# 16_HDMI.net
KiCad netlist of a schematic drawn in Altium Designer
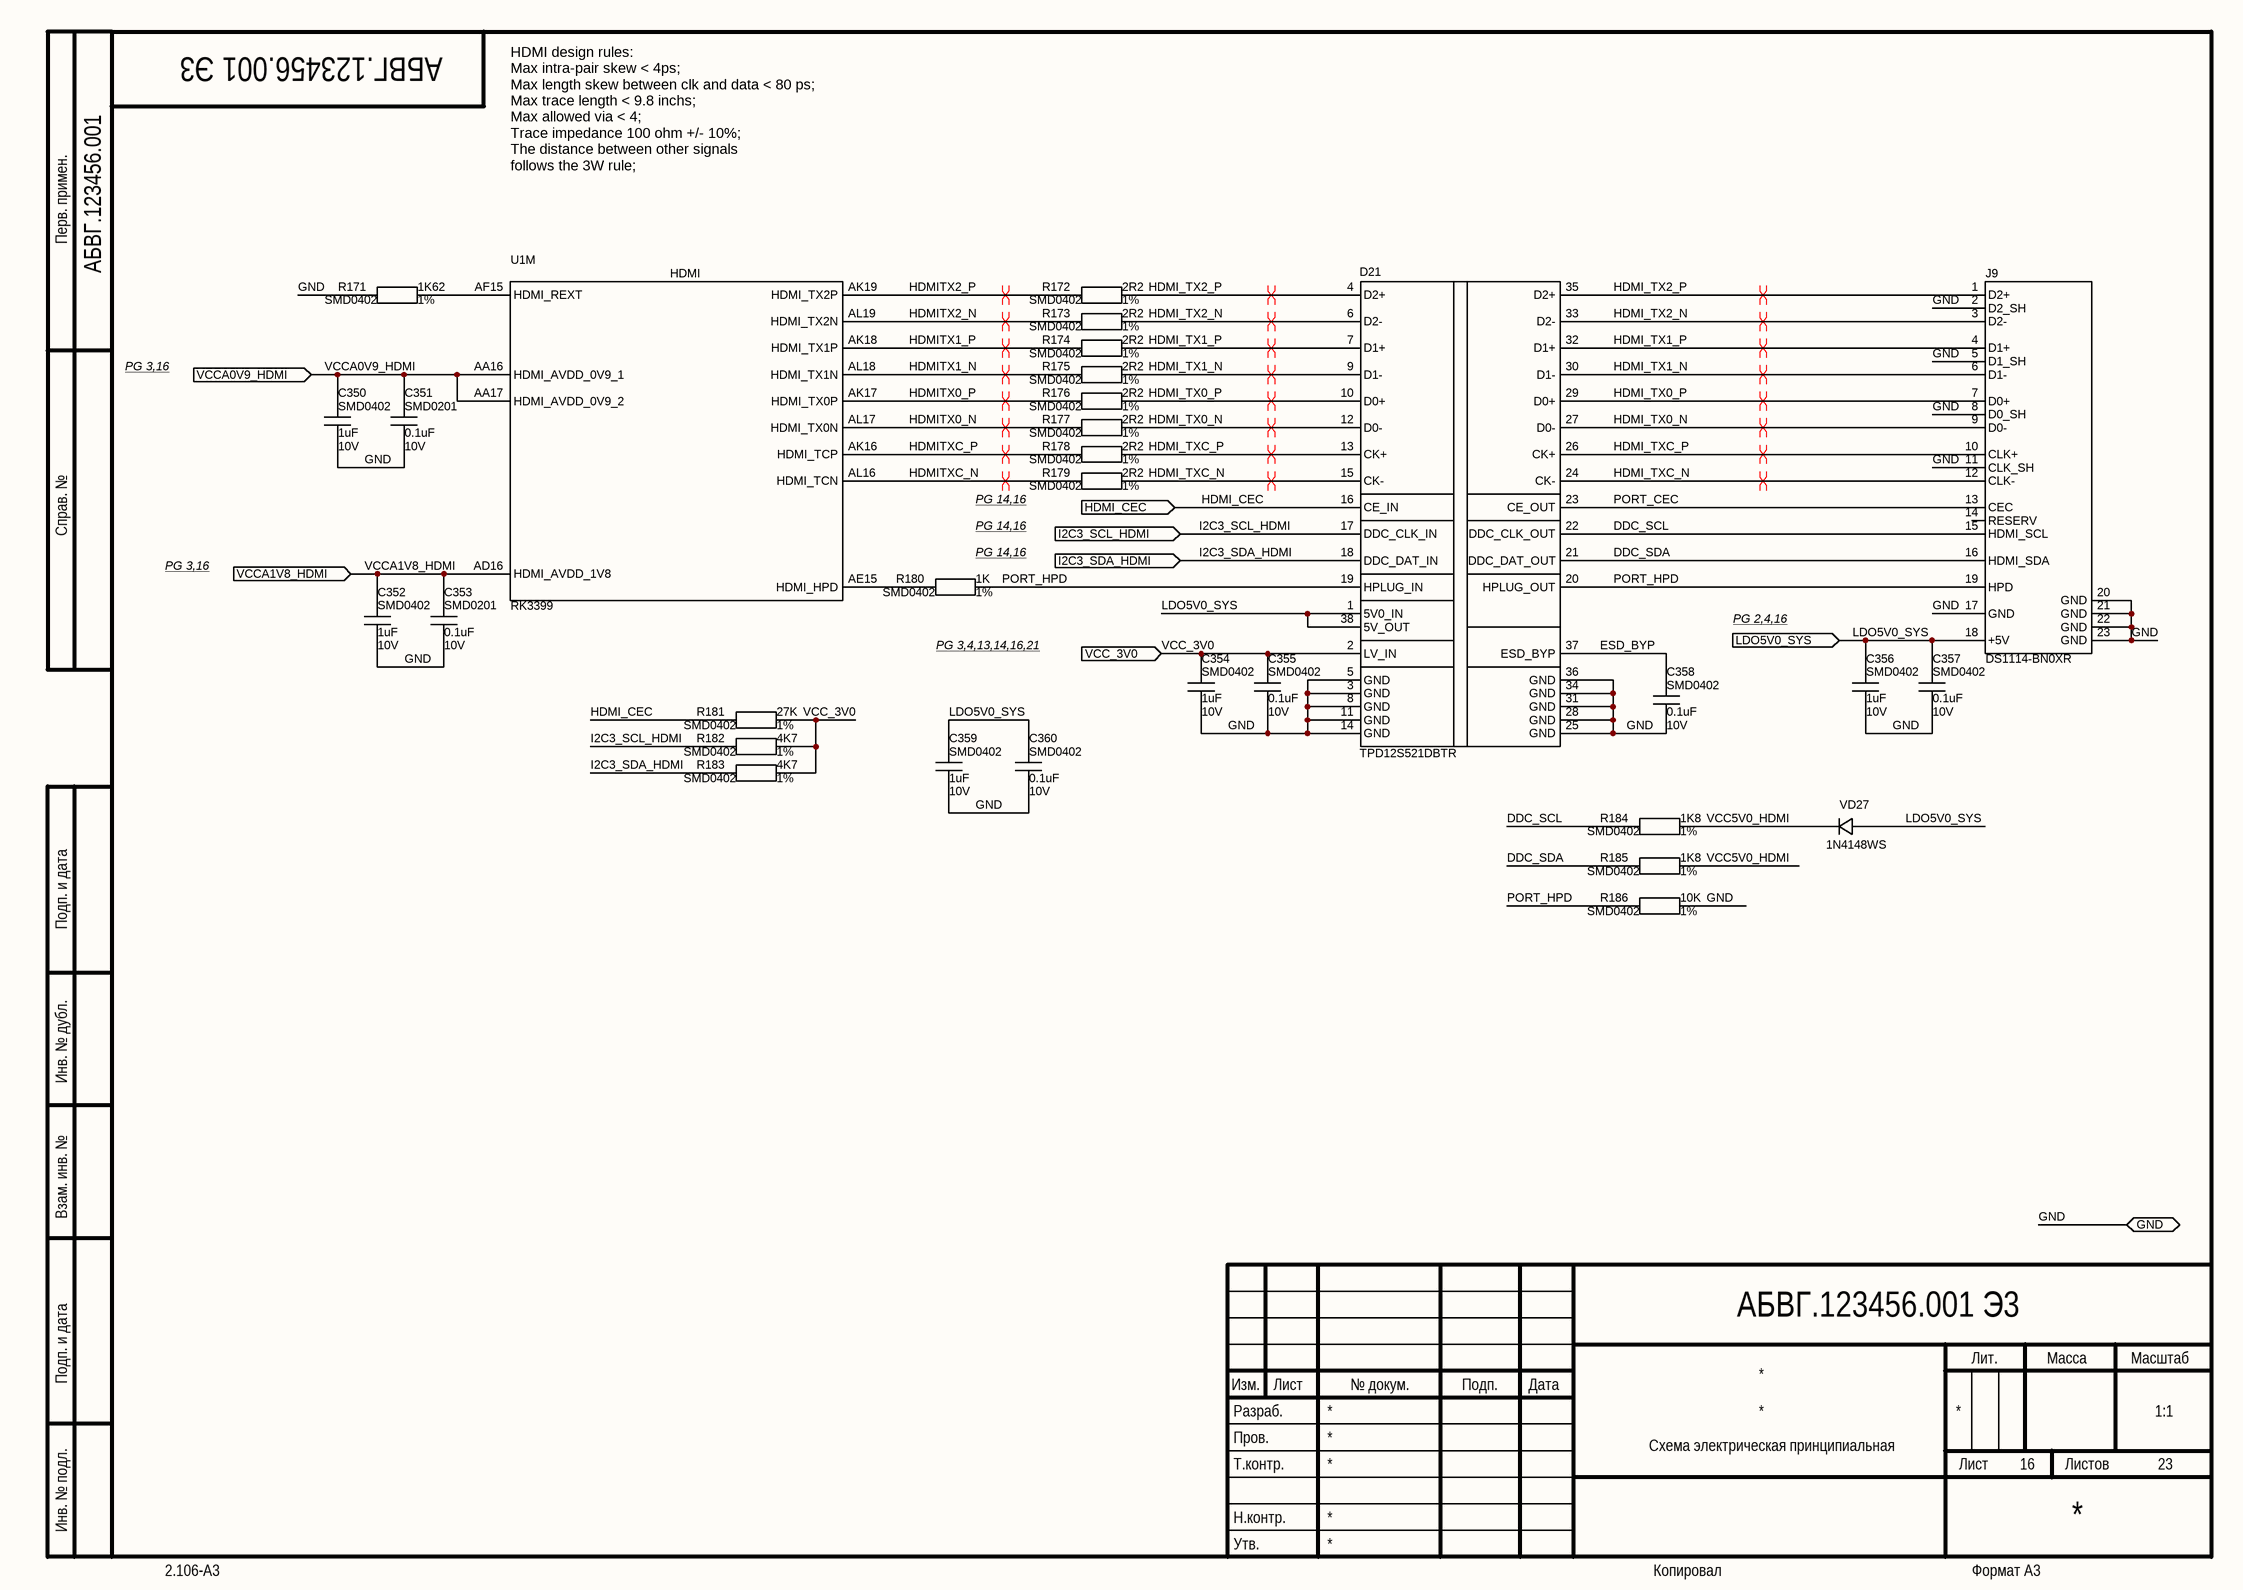
[diagram p0: 16 HDMI.SchDoc]

(export (version "E")
  (design (tool "Eeschema 10.0.6"))
  (components
    (comp (ref "C350")
      (value "1uF")
      (footprint "Didur_PcbLib_1:CAP_SMD_0402")
      (fields
        (field (name "PACKAGE") "SMD0402")
        (field (name "PARTNUMBER") "CC0402KRX5R6BB105")
        (field (name "VOLTAGE") "10V")
      )
      (libsource (lib "Didur_SchLib_1") (part "Ceramic_Cap"))
    )
    (comp (ref "C351")
      (value "0.1uF")
      (footprint "Didur_PcbLib_1:CAP_SMD_0201")
      (fields
        (field (name "PACKAGE") "SMD0201")
        (field (name "PARTNUMBER") "CC0201KRX5R6BB104")
        (field (name "VOLTAGE") "10V")
      )
      (libsource (lib "Didur_SchLib_1") (part "Ceramic_Cap"))
    )
    (comp (ref "C352")
      (value "1uF")
      (footprint "Didur_PcbLib_1:CAP_SMD_0402_small")
      (fields
        (field (name "PACKAGE") "SMD0402")
        (field (name "PARTNUMBER") "CC0402KRX5R6BB105")
        (field (name "VOLTAGE") "10V")
      )
      (libsource (lib "Didur_SchLib_1") (part "Ceramic_Cap"))
    )
    (comp (ref "C353")
      (value "0.1uF")
      (footprint "Didur_PcbLib_1:CAP_SMD_0201")
      (fields
        (field (name "PACKAGE") "SMD0201")
        (field (name "PARTNUMBER") "CC0201KRX5R6BB104")
        (field (name "VOLTAGE") "10V")
      )
      (libsource (lib "Didur_SchLib_1") (part "Ceramic_Cap"))
    )
    (comp (ref "C354")
      (value "1uF")
      (footprint "Didur_PcbLib_1:CAP_SMD_0402")
      (fields
        (field (name "PACKAGE") "SMD0402")
        (field (name "PARTNUMBER") "CC0402KRX5R6BB105")
        (field (name "VOLTAGE") "10V")
      )
      (libsource (lib "Didur_SchLib_1") (part "Ceramic_Cap"))
    )
    (comp (ref "C355")
      (value "0.1uF")
      (footprint "Didur_PcbLib_1:CAP_SMD_0402")
      (fields
        (field (name "PACKAGE") "SMD0402")
        (field (name "PARTNUMBER") "CC0402KRX5R6BB104")
        (field (name "VOLTAGE") "10V")
      )
      (libsource (lib "Didur_SchLib_1") (part "Ceramic_Cap"))
    )
    (comp (ref "C356")
      (value "1uF")
      (footprint "Didur_PcbLib_1:CAP_SMD_0402")
      (fields
        (field (name "PACKAGE") "SMD0402")
        (field (name "PARTNUMBER") "CC0402KRX5R6BB105")
        (field (name "VOLTAGE") "10V")
      )
      (libsource (lib "Didur_SchLib_1") (part "Ceramic_Cap"))
    )
    (comp (ref "C357")
      (value "0.1uF")
      (footprint "Didur_PcbLib_1:CAP_SMD_0402")
      (fields
        (field (name "PACKAGE") "SMD0402")
        (field (name "PARTNUMBER") "CC0402KRX5R6BB104")
        (field (name "VOLTAGE") "10V")
      )
      (libsource (lib "Didur_SchLib_1") (part "Ceramic_Cap"))
    )
    (comp (ref "C358")
      (value "0.1uF")
      (footprint "Didur_PcbLib_1:CAP_SMD_0402")
      (fields
        (field (name "PACKAGE") "SMD0402")
        (field (name "PARTNUMBER") "CC0402KRX5R6BB104")
        (field (name "VOLTAGE") "10V")
      )
      (libsource (lib "Didur_SchLib_1") (part "Ceramic_Cap"))
    )
    (comp (ref "C359")
      (value "1uF")
      (footprint "Didur_PcbLib_1:CAP_SMD_0402")
      (fields
        (field (name "PACKAGE") "SMD0402")
        (field (name "PARTNUMBER") "CC0402KRX5R6BB105")
        (field (name "VOLTAGE") "10V")
      )
      (libsource (lib "Didur_SchLib_1") (part "Ceramic_Cap"))
    )
    (comp (ref "C360")
      (value "0.1uF")
      (footprint "Didur_PcbLib_1:CAP_SMD_0402")
      (fields
        (field (name "PACKAGE") "SMD0402")
        (field (name "PARTNUMBER") "CC0402KRX5R6BB104")
        (field (name "VOLTAGE") "10V")
      )
      (libsource (lib "Didur_SchLib_1") (part "Ceramic_Cap"))
    )
    (comp (ref "D21")
      (value "TPD12S521DBTR")
      (footprint "Didur_PcbLib_1:TSSOP-38")
      (libsource (lib "Didur_SchLib_1") (part "TPD12S521DBTR"))
    )
    (comp (ref "J9")
      (value "DS1114-BN0XR")
      (footprint "Didur_PcbLib_1:DS1114-BN0XR")
      (libsource (lib "Didur_SchLib_1") (part "HDMI_A_1"))
    )
    (comp (ref "R171")
      (value "1K62")
      (footprint "Didur_PcbLib_1:RES_SMD_0402_SMALL")
      (fields
        (field (name "PACKAGE") "SMD0402")
        (field (name "PARTNUMBER") "RC0402FR-071K62L")
        (field (name "TOLERANCE") "1%")
      )
      (libsource (lib "Didur_SchLib_1") (part "Chip_Res"))
    )
    (comp (ref "R172")
      (value "2R2")
      (footprint "Didur_PcbLib_1:RES_SMD_0402")
      (fields
        (field (name "PACKAGE") "SMD0402")
        (field (name "PARTNUMBER") "RC0402FR-072R2L")
        (field (name "TOLERANCE") "1%")
      )
      (libsource (lib "Didur_SchLib_1") (part "Chip_Res"))
    )
    (comp (ref "R173")
      (value "2R2")
      (footprint "Didur_PcbLib_1:RES_SMD_0402")
      (fields
        (field (name "PACKAGE") "SMD0402")
        (field (name "PARTNUMBER") "RC0402FR-072R2L")
        (field (name "TOLERANCE") "1%")
      )
      (libsource (lib "Didur_SchLib_1") (part "Chip_Res"))
    )
    (comp (ref "R174")
      (value "2R2")
      (footprint "Didur_PcbLib_1:RES_SMD_0402")
      (fields
        (field (name "PACKAGE") "SMD0402")
        (field (name "PARTNUMBER") "RC0402FR-072R2L")
        (field (name "TOLERANCE") "1%")
      )
      (libsource (lib "Didur_SchLib_1") (part "Chip_Res"))
    )
    (comp (ref "R175")
      (value "2R2")
      (footprint "Didur_PcbLib_1:RES_SMD_0402")
      (fields
        (field (name "PACKAGE") "SMD0402")
        (field (name "PARTNUMBER") "RC0402FR-072R2L")
        (field (name "TOLERANCE") "1%")
      )
      (libsource (lib "Didur_SchLib_1") (part "Chip_Res"))
    )
    (comp (ref "R176")
      (value "2R2")
      (footprint "Didur_PcbLib_1:RES_SMD_0402")
      (fields
        (field (name "PACKAGE") "SMD0402")
        (field (name "PARTNUMBER") "RC0402FR-072R2L")
        (field (name "TOLERANCE") "1%")
      )
      (libsource (lib "Didur_SchLib_1") (part "Chip_Res"))
    )
    (comp (ref "R177")
      (value "2R2")
      (footprint "Didur_PcbLib_1:RES_SMD_0402")
      (fields
        (field (name "PACKAGE") "SMD0402")
        (field (name "PARTNUMBER") "RC0402FR-072R2L")
        (field (name "TOLERANCE") "1%")
      )
      (libsource (lib "Didur_SchLib_1") (part "Chip_Res"))
    )
    (comp (ref "R178")
      (value "2R2")
      (footprint "Didur_PcbLib_1:RES_SMD_0402")
      (fields
        (field (name "PACKAGE") "SMD0402")
        (field (name "PARTNUMBER") "RC0402FR-072R2L")
        (field (name "TOLERANCE") "1%")
      )
      (libsource (lib "Didur_SchLib_1") (part "Chip_Res"))
    )
    (comp (ref "R179")
      (value "2R2")
      (footprint "Didur_PcbLib_1:RES_SMD_0402")
      (fields
        (field (name "PACKAGE") "SMD0402")
        (field (name "PARTNUMBER") "RC0402FR-072R2L")
        (field (name "TOLERANCE") "1%")
      )
      (libsource (lib "Didur_SchLib_1") (part "Chip_Res"))
    )
    (comp (ref "R180")
      (value "1K")
      (footprint "Didur_PcbLib_1:RES_SMD_0402")
      (fields
        (field (name "PACKAGE") "SMD0402")
        (field (name "PARTNUMBER") "RC0402FR-071KL")
        (field (name "TOLERANCE") "1%")
      )
      (libsource (lib "Didur_SchLib_1") (part "Chip_Res"))
    )
    (comp (ref "R181")
      (value "27K")
      (footprint "Didur_PcbLib_1:RES_SMD_0402")
      (fields
        (field (name "PACKAGE") "SMD0402")
        (field (name "PARTNUMBER") "RC0402FR-0727KL")
        (field (name "TOLERANCE") "1%")
      )
      (libsource (lib "Didur_SchLib_1") (part "Chip_Res"))
    )
    (comp (ref "R182")
      (value "4K7")
      (footprint "Didur_PcbLib_1:RES_SMD_0402")
      (fields
        (field (name "PACKAGE") "SMD0402")
        (field (name "PARTNUMBER") "RC0402FR-074K7L")
        (field (name "TOLERANCE") "1%")
      )
      (libsource (lib "Didur_SchLib_1") (part "Chip_Res"))
    )
    (comp (ref "R183")
      (value "4K7")
      (footprint "Didur_PcbLib_1:RES_SMD_0402")
      (fields
        (field (name "PACKAGE") "SMD0402")
        (field (name "PARTNUMBER") "RC0402FR-074K7L")
        (field (name "TOLERANCE") "1%")
      )
      (libsource (lib "Didur_SchLib_1") (part "Chip_Res"))
    )
    (comp (ref "R184")
      (value "1K8")
      (footprint "Didur_PcbLib_1:RES_SMD_0402")
      (fields
        (field (name "PACKAGE") "SMD0402")
        (field (name "PARTNUMBER") "RC0402FR-071K8L")
        (field (name "TOLERANCE") "1%")
      )
      (libsource (lib "Didur_SchLib_1") (part "Chip_Res"))
    )
    (comp (ref "R185")
      (value "1K8")
      (footprint "Didur_PcbLib_1:RES_SMD_0402")
      (fields
        (field (name "PACKAGE") "SMD0402")
        (field (name "PARTNUMBER") "RC0402FR-071K8L")
        (field (name "TOLERANCE") "1%")
      )
      (libsource (lib "Didur_SchLib_1") (part "Chip_Res"))
    )
    (comp (ref "R186")
      (value "10K")
      (footprint "Didur_PcbLib_1:RES_SMD_0402")
      (fields
        (field (name "PACKAGE") "SMD0402")
        (field (name "PARTNUMBER") "RC0402FR-0710KL")
        (field (name "TOLERANCE") "1%")
      )
      (libsource (lib "") (part "Chip_Res_1"))
    )
    (comp (ref "U1")
      (value "RK3399")
      (footprint "BGA828C65P31X31_2100X2100X161N")
      (fields (field (name "Comment") "RK3399_FF"))
      (libsource (lib "Didur_SchLib_1") (part "RK3399_FF"))
    )
    (comp (ref "VD27")
      (value "1N4148WS")
      (footprint "SOD323")
      (fields (field (name "Comment") "Diode"))
      (libsource (lib "Didur_SchLib_1") (part "Diode"))
    )
  )
  (nets
    (net (code "1") (name "/DDC_SCL") (class "Default")
      (node (ref "D21") (pin "22") (pinfunction "DDC_CLK_OUT_22") (pintype "passive"))
      (node (ref "J9") (pin "15") (pinfunction "HDMI_SCL_15") (pintype "passive"))
      (node (ref "R184") (pin "1") (pinfunction "1_1") (pintype "passive"))
    )
    (net (code "2") (name "/DDC_SDA") (class "Default")
      (node (ref "D21") (pin "21") (pinfunction "DDC_DAT_OUT_21") (pintype "passive"))
      (node (ref "J9") (pin "16") (pinfunction "HDMI_SDA_16") (pintype "passive"))
      (node (ref "R185") (pin "1") (pinfunction "1_1") (pintype "passive"))
    )
    (net (code "3") (name "/ESD_BYP") (class "Default")
      (node (ref "C358") (pin "1") (pinfunction "1_1") (pintype "power_in"))
      (node (ref "D21") (pin "37") (pinfunction "ESD_BYP_37") (pintype "passive"))
    )
    (net (code "4") (name "/GND") (class "Default")
      (node (ref "C350") (pin "2") (pinfunction "2_2") (pintype "power_in"))
      (node (ref "C351") (pin "2") (pinfunction "2_2") (pintype "power_in"))
      (node (ref "C352") (pin "2") (pinfunction "2_2") (pintype "power_in"))
      (node (ref "C353") (pin "2") (pinfunction "2_2") (pintype "power_in"))
      (node (ref "C354") (pin "2") (pinfunction "2_2") (pintype "power_in"))
      (node (ref "C355") (pin "2") (pinfunction "2_2") (pintype "power_in"))
      (node (ref "C356") (pin "2") (pinfunction "2_2") (pintype "power_in"))
      (node (ref "C357") (pin "2") (pinfunction "2_2") (pintype "power_in"))
      (node (ref "C358") (pin "2") (pinfunction "2_2") (pintype "power_in"))
      (node (ref "C359") (pin "2") (pinfunction "2_2") (pintype "power_in"))
      (node (ref "C360") (pin "2") (pinfunction "2_2") (pintype "power_in"))
      (node (ref "D21") (pin "11") (pinfunction "GND_11") (pintype "passive"))
      (node (ref "D21") (pin "14") (pinfunction "GND_14") (pintype "passive"))
      (node (ref "D21") (pin "25") (pinfunction "GND_25") (pintype "passive"))
      (node (ref "D21") (pin "28") (pinfunction "GND_28") (pintype "passive"))
      (node (ref "D21") (pin "3") (pinfunction "GND_3") (pintype "passive"))
      (node (ref "D21") (pin "31") (pinfunction "GND_31") (pintype "passive"))
      (node (ref "D21") (pin "34") (pinfunction "GND_34") (pintype "passive"))
      (node (ref "D21") (pin "36") (pinfunction "GND_36") (pintype "passive"))
      (node (ref "D21") (pin "5") (pinfunction "GND_5") (pintype "passive"))
      (node (ref "D21") (pin "8") (pinfunction "GND_8") (pintype "passive"))
      (node (ref "J9") (pin "11") (pinfunction "CLK_SH_11") (pintype "passive"))
      (node (ref "J9") (pin "17") (pinfunction "GND_17") (pintype "passive"))
      (node (ref "J9") (pin "2") (pinfunction "D2_SH_2") (pintype "passive"))
      (node (ref "J9") (pin "20") (pinfunction "GND_20") (pintype "passive"))
      (node (ref "J9") (pin "21") (pinfunction "GND_21") (pintype "passive"))
      (node (ref "J9") (pin "22") (pinfunction "GND_22") (pintype "passive"))
      (node (ref "J9") (pin "23") (pinfunction "GND_23") (pintype "passive"))
      (node (ref "J9") (pin "5") (pinfunction "D1_SH_5") (pintype "passive"))
      (node (ref "J9") (pin "8") (pinfunction "D0_SH_8") (pintype "passive"))
      (node (ref "R171") (pin "1") (pinfunction "1_1") (pintype "passive"))
      (node (ref "R186") (pin "1") (pinfunction "1_1") (pintype "passive"))
    )
    (net (code "5") (name "/HDMITX0_N") (class "Default")
      (node (ref "R177") (pin "1") (pinfunction "1_1") (pintype "passive"))
      (node (ref "U1") (pin "AL17") (pinfunction "HDMI_TX0N_AL17") (pintype "passive"))
    )
    (net (code "6") (name "/HDMITX0_P") (class "Default")
      (node (ref "R176") (pin "1") (pinfunction "1_1") (pintype "passive"))
      (node (ref "U1") (pin "AK17") (pinfunction "HDMI_TX0P_AK17") (pintype "passive"))
    )
    (net (code "7") (name "/HDMITX1_N") (class "Default")
      (node (ref "R175") (pin "1") (pinfunction "1_1") (pintype "passive"))
      (node (ref "U1") (pin "AL18") (pinfunction "HDMI_TX1N_AL18") (pintype "passive"))
    )
    (net (code "8") (name "/HDMITX1_P") (class "Default")
      (node (ref "R174") (pin "1") (pinfunction "1_1") (pintype "passive"))
      (node (ref "U1") (pin "AK18") (pinfunction "HDMI_TX1P_AK18") (pintype "passive"))
    )
    (net (code "9") (name "/HDMITX2_N") (class "Default")
      (node (ref "R173") (pin "1") (pinfunction "1_1") (pintype "passive"))
      (node (ref "U1") (pin "AL19") (pinfunction "HDMI_TX2N_AL19") (pintype "passive"))
    )
    (net (code "10") (name "/HDMITX2_P") (class "Default")
      (node (ref "R172") (pin "1") (pinfunction "1_1") (pintype "passive"))
      (node (ref "U1") (pin "AK19") (pinfunction "HDMI_TX2P_AK19") (pintype "passive"))
    )
    (net (code "11") (name "/HDMITXC_N") (class "Default")
      (node (ref "R179") (pin "1") (pinfunction "1_1") (pintype "passive"))
      (node (ref "U1") (pin "AL16") (pinfunction "HDMI_TCN_AL16") (pintype "passive"))
    )
    (net (code "12") (name "/HDMITXC_P") (class "Default")
      (node (ref "R178") (pin "1") (pinfunction "1_1") (pintype "passive"))
      (node (ref "U1") (pin "AK16") (pinfunction "HDMI_TCP_AK16") (pintype "passive"))
    )
    (net (code "13") (name "/HDMI_CEC") (class "Default")
      (node (ref "D21") (pin "16") (pinfunction "CE_IN_16") (pintype "passive"))
      (node (ref "R181") (pin "1") (pinfunction "1_1") (pintype "passive"))
    )
    (net (code "14") (name "/HDMI_TX0_N") (class "Default")
      (node (ref "D21") (pin "12") (pinfunction "D0-_12") (pintype "passive"))
      (node (ref "D21") (pin "27") (pinfunction "D0-_27") (pintype "passive"))
      (node (ref "J9") (pin "9") (pinfunction "D0-_9") (pintype "passive"))
      (node (ref "R177") (pin "2") (pinfunction "2_2") (pintype "passive"))
    )
    (net (code "15") (name "/HDMI_TX0_P") (class "Default")
      (node (ref "D21") (pin "10") (pinfunction "D0+_10") (pintype "passive"))
      (node (ref "D21") (pin "29") (pinfunction "D0+_29") (pintype "passive"))
      (node (ref "J9") (pin "7") (pinfunction "D0+_7") (pintype "passive"))
      (node (ref "R176") (pin "2") (pinfunction "2_2") (pintype "passive"))
    )
    (net (code "16") (name "/HDMI_TX1_N") (class "Default")
      (node (ref "D21") (pin "30") (pinfunction "D1-_30") (pintype "passive"))
      (node (ref "D21") (pin "9") (pinfunction "D1-_9") (pintype "passive"))
      (node (ref "J9") (pin "6") (pinfunction "D1-_6") (pintype "passive"))
      (node (ref "R175") (pin "2") (pinfunction "2_2") (pintype "passive"))
    )
    (net (code "17") (name "/HDMI_TX1_P") (class "Default")
      (node (ref "D21") (pin "32") (pinfunction "D1+_32") (pintype "passive"))
      (node (ref "D21") (pin "7") (pinfunction "D1+_7") (pintype "passive"))
      (node (ref "J9") (pin "4") (pinfunction "D1+_4") (pintype "passive"))
      (node (ref "R174") (pin "2") (pinfunction "2_2") (pintype "passive"))
    )
    (net (code "18") (name "/HDMI_TX2_N") (class "Default")
      (node (ref "D21") (pin "33") (pinfunction "D2-_33") (pintype "passive"))
      (node (ref "D21") (pin "6") (pinfunction "D2-_6") (pintype "passive"))
      (node (ref "J9") (pin "3") (pinfunction "D2-_3") (pintype "passive"))
      (node (ref "R173") (pin "2") (pinfunction "2_2") (pintype "passive"))
    )
    (net (code "19") (name "/HDMI_TX2_P") (class "Default")
      (node (ref "D21") (pin "35") (pinfunction "D2+_35") (pintype "passive"))
      (node (ref "D21") (pin "4") (pinfunction "D2+_4") (pintype "passive"))
      (node (ref "J9") (pin "1") (pinfunction "D2+_1") (pintype "passive"))
      (node (ref "R172") (pin "2") (pinfunction "2_2") (pintype "passive"))
    )
    (net (code "20") (name "/HDMI_TXC_N") (class "Default")
      (node (ref "D21") (pin "15") (pinfunction "CK-_15") (pintype "passive"))
      (node (ref "D21") (pin "24") (pinfunction "CK-_24") (pintype "passive"))
      (node (ref "J9") (pin "12") (pinfunction "CLK-_12") (pintype "passive"))
      (node (ref "R179") (pin "2") (pinfunction "2_2") (pintype "passive"))
    )
    (net (code "21") (name "/HDMI_TXC_P") (class "Default")
      (node (ref "D21") (pin "13") (pinfunction "CK+_13") (pintype "passive"))
      (node (ref "D21") (pin "26") (pinfunction "CK+_26") (pintype "passive"))
      (node (ref "J9") (pin "10") (pinfunction "CLK+_10") (pintype "passive"))
      (node (ref "R178") (pin "2") (pinfunction "2_2") (pintype "passive"))
    )
    (net (code "22") (name "/I2C3_SCL_HDMI") (class "Default")
      (node (ref "D21") (pin "17") (pinfunction "DDC_CLK_IN_17") (pintype "passive"))
      (node (ref "R182") (pin "1") (pinfunction "1_1") (pintype "passive"))
    )
    (net (code "23") (name "/I2C3_SDA_HDMI") (class "Default")
      (node (ref "D21") (pin "18") (pinfunction "DDC_DAT_IN_18") (pintype "passive"))
      (node (ref "R183") (pin "1") (pinfunction "1_1") (pintype "passive"))
    )
    (net (code "24") (name "/LDO5V0_SYS") (class "Default")
      (node (ref "C356") (pin "1") (pinfunction "1_1") (pintype "power_in"))
      (node (ref "C357") (pin "1") (pinfunction "1_1") (pintype "power_in"))
      (node (ref "C359") (pin "1") (pinfunction "1_1") (pintype "power_in"))
      (node (ref "C360") (pin "1") (pinfunction "1_1") (pintype "power_in"))
      (node (ref "D21") (pin "1") (pinfunction "5V0_IN_1") (pintype "passive"))
      (node (ref "D21") (pin "38") (pinfunction "5V_OUT_38") (pintype "passive"))
      (node (ref "J9") (pin "18") (pinfunction "+5V_18") (pintype "passive"))
      (node (ref "VD27") (pin "1") (pinfunction "A_1") (pintype "passive"))
    )
    (net (code "25") (name "/PORT_CEC") (class "Default")
      (node (ref "D21") (pin "23") (pinfunction "CE_OUT_23") (pintype "passive"))
      (node (ref "J9") (pin "13") (pinfunction "CEC_13") (pintype "passive"))
    )
    (net (code "26") (name "/PORT_HPD") (class "Default")
      (node (ref "D21") (pin "19") (pinfunction "HPLUG_IN_19") (pintype "passive"))
      (node (ref "D21") (pin "20") (pinfunction "HPLUG_OUT_20") (pintype "passive"))
      (node (ref "J9") (pin "19") (pinfunction "HPD_19") (pintype "passive"))
      (node (ref "R180") (pin "2") (pinfunction "2_2") (pintype "passive"))
      (node (ref "R186") (pin "2") (pinfunction "2_2") (pintype "passive"))
    )
    (net (code "27") (name "/VCC5V0_HDMI") (class "Default")
      (node (ref "R184") (pin "2") (pinfunction "2_2") (pintype "passive"))
      (node (ref "R185") (pin "2") (pinfunction "2_2") (pintype "passive"))
      (node (ref "VD27") (pin "2") (pinfunction "C_2") (pintype "passive"))
    )
    (net (code "28") (name "/VCCA0V9_HDMI") (class "Default")
      (node (ref "C350") (pin "1") (pinfunction "1_1") (pintype "power_in"))
      (node (ref "C351") (pin "1") (pinfunction "1_1") (pintype "power_in"))
      (node (ref "U1") (pin "AA16") (pinfunction "HDMI_AVDD_0V9_1_AA16") (pintype "passive"))
      (node (ref "U1") (pin "AA17") (pinfunction "HDMI_AVDD_0V9_2_AA17") (pintype "passive"))
    )
    (net (code "29") (name "/VCCA1V8_HDMI") (class "Default")
      (node (ref "C352") (pin "1") (pinfunction "1_1") (pintype "power_in"))
      (node (ref "C353") (pin "1") (pinfunction "1_1") (pintype "power_in"))
      (node (ref "U1") (pin "AD16") (pinfunction "HDMI_AVDD_1V8_AD16") (pintype "passive"))
    )
    (net (code "30") (name "/VCC_3V0") (class "Default")
      (node (ref "C354") (pin "1") (pinfunction "1_1") (pintype "power_in"))
      (node (ref "C355") (pin "1") (pinfunction "1_1") (pintype "power_in"))
      (node (ref "D21") (pin "2") (pinfunction "LV_IN_2") (pintype "passive"))
      (node (ref "R181") (pin "2") (pinfunction "2_2") (pintype "passive"))
      (node (ref "R182") (pin "2") (pinfunction "2_2") (pintype "passive"))
      (node (ref "R183") (pin "2") (pinfunction "2_2") (pintype "passive"))
    )
    (net (code "31") (name "Net-(U1M-HDMI_HPD)") (class "Default")
      (node (ref "R180") (pin "1") (pinfunction "1_1") (pintype "passive"))
      (node (ref "U1") (pin "AE15") (pinfunction "HDMI_HPD_AE15") (pintype "passive"))
    )
    (net (code "32") (name "Net-(U1M-HDMI_REXT)") (class "Default")
      (node (ref "R171") (pin "2") (pinfunction "2_2") (pintype "passive"))
      (node (ref "U1") (pin "AF15") (pinfunction "HDMI_REXT_AF15") (pintype "passive"))
    )
    (net (code "33") (name "unconnected-(J9-RESERV-Pad14)") (class "Default")
      (node (ref "J9") (pin "14") (pinfunction "RESERV_14") (pintype "passive"))
    )
  )
)
